# BATT_CONN.net
KiCad netlist of a schematic drawn in EAGLE
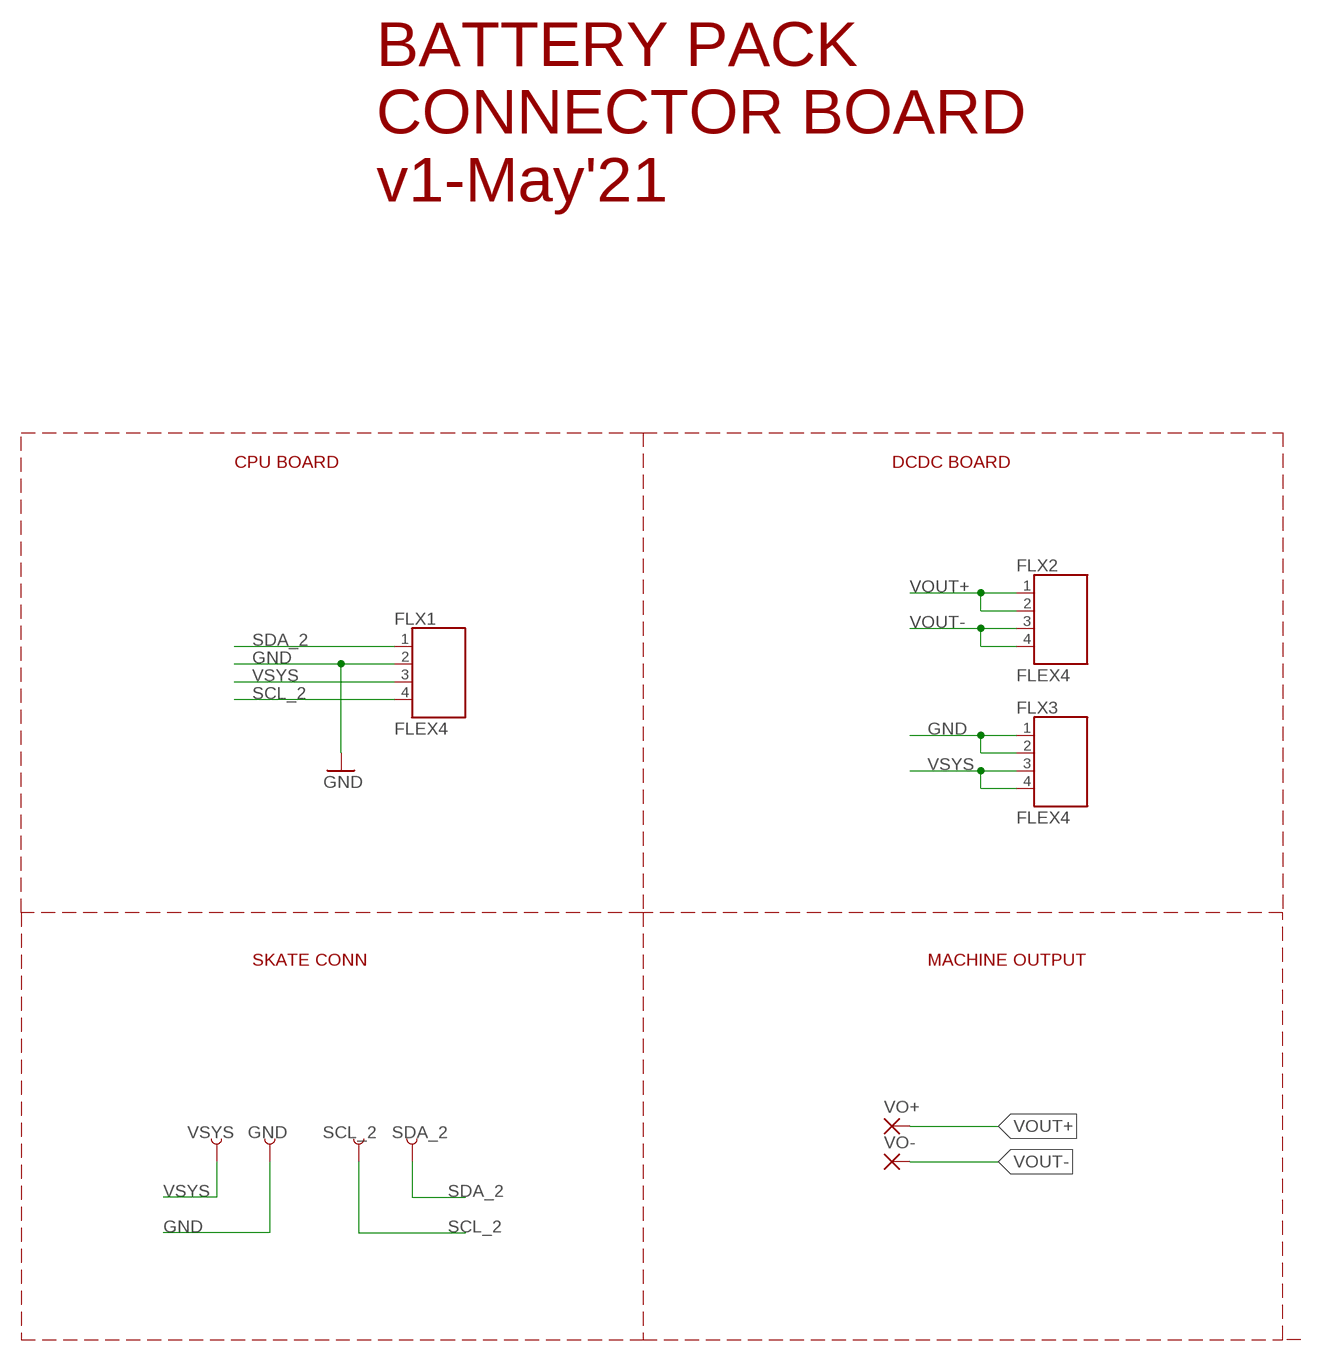
[diagram p0: schematic, sheet 1]

(export (version "E")
  (design (tool "Eeschema 10.0.6"))
  (components
    (comp (ref "FLX1")
      (value "FLEX4")
      (footprint "eagle-import:FLEX4")
      (libsource (lib "eagle-import") (part "FLEX4"))
    )
    (comp (ref "FLX2")
      (value "FLEX4")
      (footprint "eagle-import:FLEX4")
      (libsource (lib "eagle-import") (part "FLEX4"))
    )
    (comp (ref "FLX3")
      (value "FLEX4")
      (footprint "eagle-import:FLEX4")
      (libsource (lib "eagle-import") (part "FLEX4"))
    )
    (comp (ref "GND")
      (value "TEST-POINT3")
      (footprint "eagle-import:PAD.03X.03")
      (libsource (lib "eagle-import") (part "TEST-POINT3"))
    )
    (comp (ref "SCL_2")
      (value "TEST-POINT3")
      (footprint "eagle-import:PAD.03X.03")
      (libsource (lib "eagle-import") (part "TEST-POINT3"))
    )
    (comp (ref "SDA_2")
      (value "TEST-POINT3")
      (footprint "eagle-import:PAD.03X.03")
      (libsource (lib "eagle-import") (part "TEST-POINT3"))
    )
    (comp (ref "VO+")
      (value "SMD5")
      (footprint "eagle-import:SMD2,54-5,08")
      (libsource (lib "eagle-import") (part "SMD5"))
    )
    (comp (ref "VO-")
      (value "SMD5")
      (footprint "eagle-import:SMD2,54-5,08")
      (libsource (lib "eagle-import") (part "SMD5"))
    )
    (comp (ref "VSYS")
      (value "TEST-POINT3")
      (footprint "eagle-import:PAD.03X.03")
      (libsource (lib "eagle-import") (part "TEST-POINT3"))
    )
  )
  (nets
    (net (code "1") (name "/SCL_2") (class "Default")
      (node (ref "FLX1") (pin "4") (pinfunction "4_4") (pintype "passive"))
      (node (ref "SCL_2") (pin "P$1") (pinfunction "1_P$1") (pintype "bidirectional"))
    )
    (net (code "2") (name "/SDA_2") (class "Default")
      (node (ref "FLX1") (pin "1") (pinfunction "1_1") (pintype "passive"))
      (node (ref "SDA_2") (pin "P$1") (pinfunction "1_P$1") (pintype "bidirectional"))
    )
    (net (code "3") (name "/VSYS") (class "Default")
      (node (ref "FLX1") (pin "3") (pinfunction "3_3") (pintype "passive"))
      (node (ref "FLX3") (pin "3") (pinfunction "3_3") (pintype "passive"))
      (node (ref "FLX3") (pin "4") (pinfunction "4_4") (pintype "passive"))
      (node (ref "VSYS") (pin "P$1") (pinfunction "1_P$1") (pintype "bidirectional"))
    )
    (net (code "4") (name "GND") (class "Default")
      (node (ref "FLX1") (pin "2") (pinfunction "2_2") (pintype "passive"))
      (node (ref "FLX3") (pin "1") (pinfunction "1_1") (pintype "passive"))
      (node (ref "FLX3") (pin "2") (pinfunction "2_2") (pintype "passive"))
      (node (ref "GND") (pin "P$1") (pinfunction "1_P$1") (pintype "bidirectional"))
    )
    (net (code "5") (name "VOUT+") (class "Default")
      (node (ref "FLX2") (pin "1") (pinfunction "1_1") (pintype "passive"))
      (node (ref "FLX2") (pin "2") (pinfunction "2_2") (pintype "passive"))
      (node (ref "VO+") (pin "1") (pinfunction "P_1") (pintype "passive"))
    )
    (net (code "6") (name "VOUT-") (class "Default")
      (node (ref "FLX2") (pin "3") (pinfunction "3_3") (pintype "passive"))
      (node (ref "FLX2") (pin "4") (pinfunction "4_4") (pintype "passive"))
      (node (ref "VO-") (pin "1") (pinfunction "P_1") (pintype "passive"))
    )
  )
)
